# detector.net
KiCad netlist of a schematic drawn in EAGLE
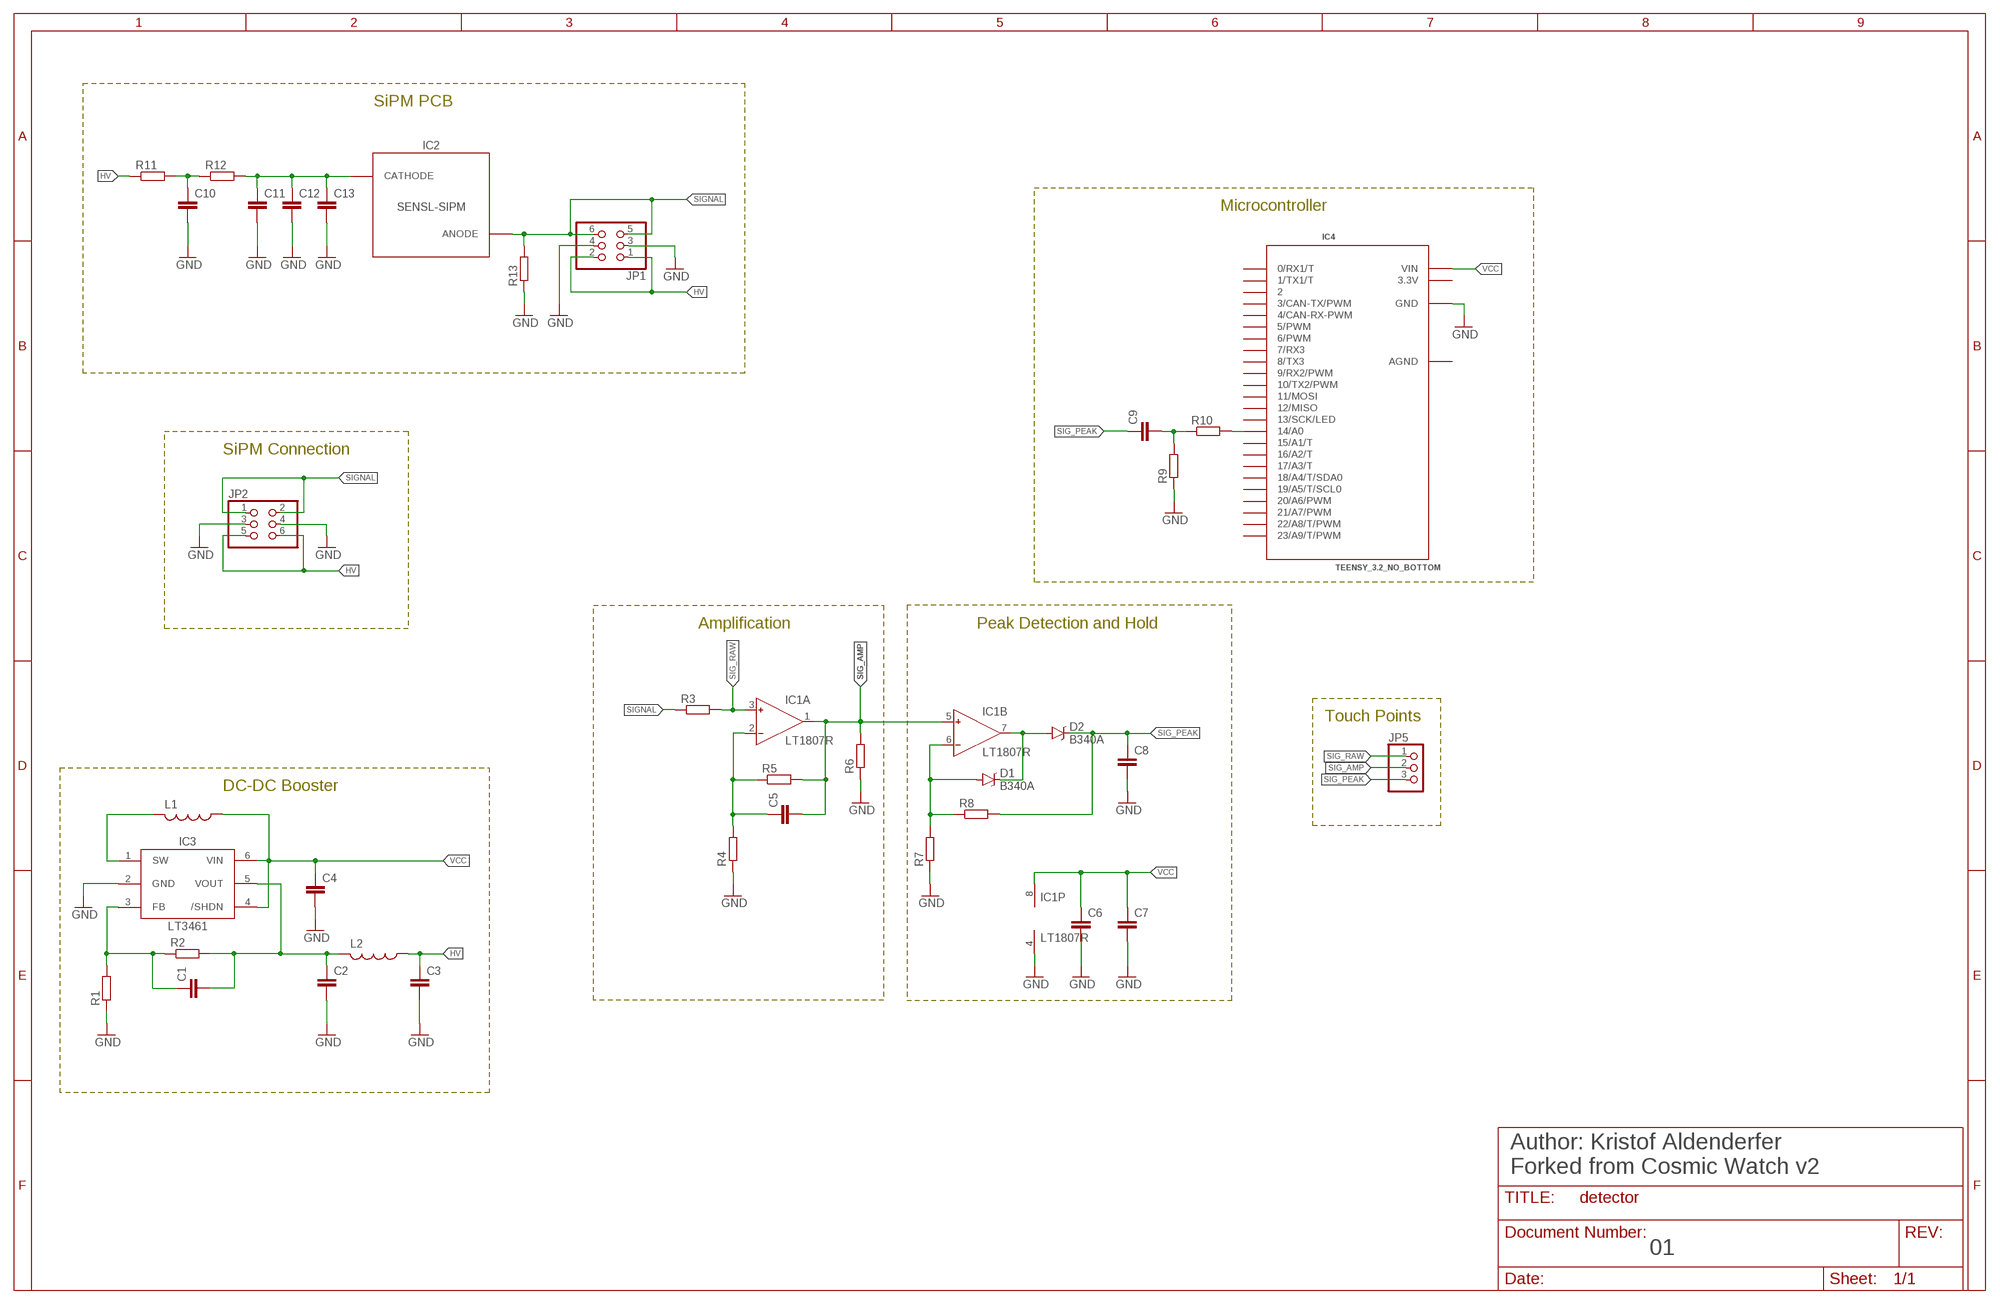
[diagram p0: schematic, sheet 1]

(export (version "E")
  (design (tool "Eeschema 10.0.6"))
  (components
    (comp (ref "C1")
      (value "C-EUC0805")
      (footprint "eagle-import:C0805")
      (libsource (lib "eagle-import") (part "C-EUC0805"))
    )
    (comp (ref "C2")
      (value "C-EUC0805")
      (footprint "eagle-import:C0805")
      (libsource (lib "eagle-import") (part "C-EUC0805"))
    )
    (comp (ref "C3")
      (value "C-EUC0805")
      (footprint "eagle-import:C0805")
      (libsource (lib "eagle-import") (part "C-EUC0805"))
    )
    (comp (ref "C4")
      (value "C-EUC0805")
      (footprint "eagle-import:C0805")
      (libsource (lib "eagle-import") (part "C-EUC0805"))
    )
    (comp (ref "C5")
      (value "C-EUC0805")
      (footprint "eagle-import:C0805")
      (libsource (lib "eagle-import") (part "C-EUC0805"))
    )
    (comp (ref "C6")
      (value "C-EUC0805")
      (footprint "eagle-import:C0805")
      (libsource (lib "eagle-import") (part "C-EUC0805"))
    )
    (comp (ref "C7")
      (value "C-EUC0805")
      (footprint "eagle-import:C0805")
      (libsource (lib "eagle-import") (part "C-EUC0805"))
    )
    (comp (ref "C8")
      (value "C-EUC0805")
      (footprint "eagle-import:C0805")
      (libsource (lib "eagle-import") (part "C-EUC0805"))
    )
    (comp (ref "C9")
      (value "C-EUC0805")
      (footprint "eagle-import:C0805")
      (libsource (lib "eagle-import") (part "C-EUC0805"))
    )
    (comp (ref "C10")
      (value "C-EUC0805")
      (footprint "eagle-import:C0805")
      (libsource (lib "eagle-import") (part "C-EUC0805"))
    )
    (comp (ref "C11")
      (value "C-EUC0805")
      (footprint "eagle-import:C0805")
      (libsource (lib "eagle-import") (part "C-EUC0805"))
    )
    (comp (ref "C12")
      (value "C-EUC0805")
      (footprint "eagle-import:C0805")
      (libsource (lib "eagle-import") (part "C-EUC0805"))
    )
    (comp (ref "C13")
      (value "C-EUC0805")
      (footprint "eagle-import:C0805")
      (libsource (lib "eagle-import") (part "C-EUC0805"))
    )
    (comp (ref "D1")
      (value "B340A")
      (footprint "eagle-import:SMA-DIODE")
      (libsource (lib "eagle-import") (part "DIODE-SCHOTTKY-B340A"))
    )
    (comp (ref "D2")
      (value "B340A")
      (footprint "eagle-import:SMA-DIODE")
      (libsource (lib "eagle-import") (part "DIODE-SCHOTTKY-B340A"))
    )
    (comp (ref "IC1")
      (value "LT1807R")
      (footprint "eagle-import:SO8")
      (fields (field (name "MF") "ALTERA CORPORATION") (field (name "MPN") "AD746JRZ"))
      (libsource (lib "eagle-import") (part "LT1807R"))
    )
    (comp (ref "IC2")
      (value "SENSL-SIPM")
      (footprint "eagle-import:MICROFC-60035")
      (libsource (lib "eagle-import") (part "SENSL-SIPM"))
    )
    (comp (ref "IC3")
      (value "LT3461")
      (footprint "eagle-import:SOT23-6")
      (libsource (lib "eagle-import") (part "LT3461"))
    )
    (comp (ref "IC4")
      (value "TEENSY_3.2_NO_BOTTOM")
      (footprint "eagle-import:TEENSY_3.2_NO_BOTTOM")
      (libsource (lib "eagle-import") (part "TEENSY_3.2_NO_BOTTOM"))
    )
    (comp (ref "JP1")
      (value "PINHD-2X3")
      (footprint "eagle-import:2X03")
      (libsource (lib "eagle-import") (part "PINHD-2X3"))
    )
    (comp (ref "JP2")
      (value "PINHD-2X3")
      (footprint "eagle-import:2X03")
      (libsource (lib "eagle-import") (part "PINHD-2X3"))
    )
    (comp (ref "JP5")
      (value "PINHD-1X3")
      (footprint "eagle-import:1X03")
      (libsource (lib "eagle-import") (part "PINHD-1X3"))
    )
    (comp (ref "L1")
      (value "L-USL2012C")
      (footprint "eagle-import:L2012C")
      (libsource (lib "eagle-import") (part "L-USL2012C"))
    )
    (comp (ref "L2")
      (value "L-USL2012C")
      (footprint "eagle-import:L2012C")
      (libsource (lib "eagle-import") (part "L-USL2012C"))
    )
    (comp (ref "R1")
      (value "R-EU_M0805")
      (footprint "eagle-import:M0805")
      (libsource (lib "eagle-import") (part "R-EU_M0805"))
    )
    (comp (ref "R2")
      (value "R-EU_M0805")
      (footprint "eagle-import:M0805")
      (libsource (lib "eagle-import") (part "R-EU_M0805"))
    )
    (comp (ref "R3")
      (value "R-EU_M0805")
      (footprint "eagle-import:M0805")
      (libsource (lib "eagle-import") (part "R-EU_M0805"))
    )
    (comp (ref "R4")
      (value "R-EU_M0805")
      (footprint "eagle-import:M0805")
      (libsource (lib "eagle-import") (part "R-EU_M0805"))
    )
    (comp (ref "R5")
      (value "R-EU_M0805")
      (footprint "eagle-import:M0805")
      (libsource (lib "eagle-import") (part "R-EU_M0805"))
    )
    (comp (ref "R6")
      (value "R-EU_M0805")
      (footprint "eagle-import:M0805")
      (libsource (lib "eagle-import") (part "R-EU_M0805"))
    )
    (comp (ref "R7")
      (value "R-EU_M0805")
      (footprint "eagle-import:M0805")
      (libsource (lib "eagle-import") (part "R-EU_M0805"))
    )
    (comp (ref "R8")
      (value "R-EU_M0805")
      (footprint "eagle-import:M0805")
      (libsource (lib "eagle-import") (part "R-EU_M0805"))
    )
    (comp (ref "R9")
      (value "R-EU_M0805")
      (footprint "eagle-import:M0805")
      (libsource (lib "eagle-import") (part "R-EU_M0805"))
    )
    (comp (ref "R10")
      (value "R-EU_M0805")
      (footprint "eagle-import:M0805")
      (libsource (lib "eagle-import") (part "R-EU_M0805"))
    )
    (comp (ref "R11")
      (value "R-EU_M0805")
      (footprint "eagle-import:M0805")
      (libsource (lib "eagle-import") (part "R-EU_M0805"))
    )
    (comp (ref "R12")
      (value "R-EU_M0805")
      (footprint "eagle-import:M0805")
      (libsource (lib "eagle-import") (part "R-EU_M0805"))
    )
    (comp (ref "R13")
      (value "R-EU_M0805")
      (footprint "eagle-import:M0805")
      (libsource (lib "eagle-import") (part "R-EU_M0805"))
    )
  )
  (nets
    (net (code "1") (name "/3.3V") (class "Default")
      (node (ref "IC4") (pin "3.3V") (pinfunction "3.3V_3.3V") (pintype "power_in"))
    )
    (net (code "2") (name "/AGND") (class "Default")
      (node (ref "IC4") (pin "AGND") (pinfunction "AGND_AGND") (pintype "power_in"))
    )
    (net (code "3") (name "GND") (class "Default")
      (node (ref "C10") (pin "2") (pinfunction "2_2") (pintype "passive"))
      (node (ref "C11") (pin "2") (pinfunction "2_2") (pintype "passive"))
      (node (ref "C12") (pin "2") (pinfunction "2_2") (pintype "passive"))
      (node (ref "C13") (pin "2") (pinfunction "2_2") (pintype "passive"))
      (node (ref "C2") (pin "2") (pinfunction "2_2") (pintype "passive"))
      (node (ref "C3") (pin "2") (pinfunction "2_2") (pintype "passive"))
      (node (ref "C4") (pin "2") (pinfunction "2_2") (pintype "passive"))
      (node (ref "C6") (pin "2") (pinfunction "2_2") (pintype "passive"))
      (node (ref "C7") (pin "2") (pinfunction "2_2") (pintype "passive"))
      (node (ref "C8") (pin "2") (pinfunction "2_2") (pintype "passive"))
      (node (ref "IC1") (pin "4") (pinfunction "V-_4") (pintype "power_in"))
      (node (ref "IC3") (pin "2") (pinfunction "GND_2") (pintype "power_in"))
      (node (ref "IC4") (pin "GND") (pinfunction "GND_GND") (pintype "power_in"))
      (node (ref "JP1") (pin "3") (pinfunction "3_3") (pintype "passive"))
      (node (ref "JP1") (pin "4") (pinfunction "4_4") (pintype "passive"))
      (node (ref "JP2") (pin "3") (pinfunction "3_3") (pintype "passive"))
      (node (ref "JP2") (pin "4") (pinfunction "4_4") (pintype "passive"))
      (node (ref "R1") (pin "1") (pinfunction "1_1") (pintype "passive"))
      (node (ref "R13") (pin "1") (pinfunction "1_1") (pintype "passive"))
      (node (ref "R4") (pin "1") (pinfunction "1_1") (pintype "passive"))
      (node (ref "R6") (pin "1") (pinfunction "1_1") (pintype "passive"))
      (node (ref "R7") (pin "1") (pinfunction "1_1") (pintype "passive"))
      (node (ref "R9") (pin "1") (pinfunction "1_1") (pintype "passive"))
    )
    (net (code "4") (name "HV") (class "Default")
      (node (ref "C3") (pin "1") (pinfunction "1_1") (pintype "passive"))
      (node (ref "JP1") (pin "1") (pinfunction "1_1") (pintype "passive"))
      (node (ref "JP1") (pin "2") (pinfunction "2_2") (pintype "passive"))
      (node (ref "JP2") (pin "5") (pinfunction "5_5") (pintype "passive"))
      (node (ref "JP2") (pin "6") (pinfunction "6_6") (pintype "passive"))
      (node (ref "L2") (pin "1") (pinfunction "1_1") (pintype "passive"))
      (node (ref "R11") (pin "1") (pinfunction "1_1") (pintype "passive"))
    )
    (net (code "5") (name "Net-(C9-Pad2)") (class "Default")
      (node (ref "C9") (pin "2") (pinfunction "2_2") (pintype "passive"))
      (node (ref "R10") (pin "1") (pinfunction "1_1") (pintype "passive"))
      (node (ref "R9") (pin "2") (pinfunction "2_2") (pintype "passive"))
    )
    (net (code "6") (name "Net-(C10-Pad1)") (class "Default")
      (node (ref "C10") (pin "1") (pinfunction "1_1") (pintype "passive"))
      (node (ref "R11") (pin "2") (pinfunction "2_2") (pintype "passive"))
      (node (ref "R12") (pin "1") (pinfunction "1_1") (pintype "passive"))
    )
    (net (code "7") (name "Net-(C11-Pad1)") (class "Default")
      (node (ref "C11") (pin "1") (pinfunction "1_1") (pintype "passive"))
      (node (ref "C12") (pin "1") (pinfunction "1_1") (pintype "passive"))
      (node (ref "C13") (pin "1") (pinfunction "1_1") (pintype "passive"))
      (node (ref "IC2") (pin "CATHODE") (pinfunction "CATHODE_CATHODE") (pintype "bidirectional"))
      (node (ref "R12") (pin "2") (pinfunction "2_2") (pintype "passive"))
    )
    (net (code "8") (name "Net-(IC1A-IN-)") (class "Default")
      (node (ref "C5") (pin "1") (pinfunction "1_1") (pintype "passive"))
      (node (ref "IC1") (pin "2") (pinfunction "IN-_2") (pintype "input"))
      (node (ref "R4") (pin "2") (pinfunction "2_2") (pintype "passive"))
      (node (ref "R5") (pin "1") (pinfunction "1_1") (pintype "passive"))
    )
    (net (code "9") (name "Net-(IC1B-IN-)") (class "Default")
      (node (ref "D1") (pin "A") (pinfunction "A_A") (pintype "passive"))
      (node (ref "IC1") (pin "6") (pinfunction "IN-_6") (pintype "input"))
      (node (ref "R7") (pin "2") (pinfunction "2_2") (pintype "passive"))
      (node (ref "R8") (pin "1") (pinfunction "1_1") (pintype "passive"))
    )
    (net (code "10") (name "Net-(IC1B-OUT)") (class "Default")
      (node (ref "D1") (pin "C") (pinfunction "C_C") (pintype "passive"))
      (node (ref "D2") (pin "A") (pinfunction "A_A") (pintype "passive"))
      (node (ref "IC1") (pin "7") (pinfunction "OUT_7") (pintype "output"))
    )
    (net (code "11") (name "Net-(IC3-FB)") (class "Default")
      (node (ref "C1") (pin "1") (pinfunction "1_1") (pintype "passive"))
      (node (ref "IC3") (pin "3") (pinfunction "FB_3") (pintype "input"))
      (node (ref "R1") (pin "2") (pinfunction "2_2") (pintype "passive"))
      (node (ref "R2") (pin "1") (pinfunction "1_1") (pintype "passive"))
    )
    (net (code "12") (name "Net-(IC3-SW)") (class "Default")
      (node (ref "IC3") (pin "1") (pinfunction "SW_1") (pintype "output"))
      (node (ref "L1") (pin "2") (pinfunction "2_2") (pintype "passive"))
    )
    (net (code "13") (name "Net-(IC3-VOUT)") (class "Default")
      (node (ref "C1") (pin "2") (pinfunction "2_2") (pintype "passive"))
      (node (ref "C2") (pin "1") (pinfunction "1_1") (pintype "passive"))
      (node (ref "IC3") (pin "5") (pinfunction "VOUT_5") (pintype "output"))
      (node (ref "L2") (pin "2") (pinfunction "2_2") (pintype "passive"))
      (node (ref "R2") (pin "2") (pinfunction "2_2") (pintype "passive"))
    )
    (net (code "14") (name "Net-(IC4-Pad14{slash}A0)") (class "Default")
      (node (ref "IC4") (pin "14/A0") (pinfunction "14/A0_14/A0") (pintype "bidirectional"))
      (node (ref "R10") (pin "2") (pinfunction "2_2") (pintype "passive"))
    )
    (net (code "15") (name "SIGNAL") (class "Default")
      (node (ref "IC2") (pin "ANODE") (pinfunction "ANODE_ANODE") (pintype "bidirectional"))
      (node (ref "JP1") (pin "5") (pinfunction "5_5") (pintype "passive"))
      (node (ref "JP1") (pin "6") (pinfunction "6_6") (pintype "passive"))
      (node (ref "JP2") (pin "1") (pinfunction "1_1") (pintype "passive"))
      (node (ref "JP2") (pin "2") (pinfunction "2_2") (pintype "passive"))
      (node (ref "R13") (pin "2") (pinfunction "2_2") (pintype "passive"))
      (node (ref "R3") (pin "1") (pinfunction "1_1") (pintype "passive"))
    )
    (net (code "16") (name "SIG_AMP") (class "Default")
      (node (ref "C5") (pin "2") (pinfunction "2_2") (pintype "passive"))
      (node (ref "IC1") (pin "1") (pinfunction "OUT_1") (pintype "output"))
      (node (ref "IC1") (pin "5") (pinfunction "IN+_5") (pintype "input"))
      (node (ref "JP5") (pin "2") (pinfunction "2_2") (pintype "passive"))
      (node (ref "R5") (pin "2") (pinfunction "2_2") (pintype "passive"))
      (node (ref "R6") (pin "2") (pinfunction "2_2") (pintype "passive"))
    )
    (net (code "17") (name "SIG_PEAK") (class "Default")
      (node (ref "C8") (pin "1") (pinfunction "1_1") (pintype "passive"))
      (node (ref "C9") (pin "1") (pinfunction "1_1") (pintype "passive"))
      (node (ref "D2") (pin "C") (pinfunction "C_C") (pintype "passive"))
      (node (ref "JP5") (pin "3") (pinfunction "3_3") (pintype "passive"))
      (node (ref "R8") (pin "2") (pinfunction "2_2") (pintype "passive"))
    )
    (net (code "18") (name "SIG_RAW") (class "Default")
      (node (ref "IC1") (pin "3") (pinfunction "IN+_3") (pintype "input"))
      (node (ref "JP5") (pin "1") (pinfunction "1_1") (pintype "passive"))
      (node (ref "R3") (pin "2") (pinfunction "2_2") (pintype "passive"))
    )
    (net (code "19") (name "VCC") (class "Default")
      (node (ref "C4") (pin "1") (pinfunction "1_1") (pintype "passive"))
      (node (ref "C6") (pin "1") (pinfunction "1_1") (pintype "passive"))
      (node (ref "C7") (pin "1") (pinfunction "1_1") (pintype "passive"))
      (node (ref "IC1") (pin "8") (pinfunction "V+_8") (pintype "power_in"))
      (node (ref "IC3") (pin "4") (pinfunction "/SHDN_4") (pintype "input"))
      (node (ref "IC3") (pin "6") (pinfunction "VIN_6") (pintype "input"))
      (node (ref "IC4") (pin "VIN") (pinfunction "VIN_VIN") (pintype "power_in"))
      (node (ref "L1") (pin "1") (pinfunction "1_1") (pintype "passive"))
    )
    (net (code "20") (name "unconnected-(IC4-0{slash}RX1{slash}T-Pad0)") (class "Default")
      (node (ref "IC4") (pin "0") (pinfunction "0/RX1/T_0") (pintype "bidirectional"))
    )
    (net (code "21") (name "unconnected-(IC4-1{slash}TX1{slash}T-Pad1)") (class "Default")
      (node (ref "IC4") (pin "1") (pinfunction "1/TX1/T_1") (pintype "bidirectional"))
    )
    (net (code "22") (name "unconnected-(IC4-3{slash}CAN-TX{slash}PWM-Pad3)") (class "Default")
      (node (ref "IC4") (pin "3") (pinfunction "3/CAN-TX/PWM_3") (pintype "bidirectional"))
    )
    (net (code "23") (name "unconnected-(IC4-4{slash}CAN-RX-PWM-Pad4)") (class "Default")
      (node (ref "IC4") (pin "4") (pinfunction "4/CAN-RX-PWM_4") (pintype "bidirectional"))
    )
    (net (code "24") (name "unconnected-(IC4-5{slash}PWM-Pad5)") (class "Default")
      (node (ref "IC4") (pin "5") (pinfunction "5/PWM_5") (pintype "bidirectional"))
    )
    (net (code "25") (name "unconnected-(IC4-6{slash}PWM-Pad6)") (class "Default")
      (node (ref "IC4") (pin "6") (pinfunction "6/PWM_6") (pintype "bidirectional"))
    )
    (net (code "26") (name "unconnected-(IC4-7{slash}RX3-Pad7)") (class "Default")
      (node (ref "IC4") (pin "7") (pinfunction "7/RX3_7") (pintype "bidirectional"))
    )
    (net (code "27") (name "unconnected-(IC4-8{slash}TX3-Pad8)") (class "Default")
      (node (ref "IC4") (pin "8") (pinfunction "8/TX3_8") (pintype "bidirectional"))
    )
    (net (code "28") (name "unconnected-(IC4-9{slash}RX2{slash}PWM-Pad9)") (class "Default")
      (node (ref "IC4") (pin "9") (pinfunction "9/RX2/PWM_9") (pintype "bidirectional"))
    )
    (net (code "29") (name "unconnected-(IC4-10{slash}TX2{slash}PWM-Pad10)") (class "Default")
      (node (ref "IC4") (pin "10") (pinfunction "10/TX2/PWM_10") (pintype "bidirectional"))
    )
    (net (code "30") (name "unconnected-(IC4-11{slash}MOSI-Pad11)") (class "Default")
      (node (ref "IC4") (pin "11") (pinfunction "11/MOSI_11") (pintype "bidirectional"))
    )
    (net (code "31") (name "unconnected-(IC4-12{slash}MISO-Pad12)") (class "Default")
      (node (ref "IC4") (pin "12") (pinfunction "12/MISO_12") (pintype "bidirectional"))
    )
    (net (code "32") (name "unconnected-(IC4-13{slash}SCK{slash}LED-Pad13)") (class "Default")
      (node (ref "IC4") (pin "13") (pinfunction "13/SCK/LED_13") (pintype "bidirectional"))
    )
    (net (code "33") (name "unconnected-(IC4-15{slash}A1{slash}T-Pad15{slash}A1)") (class "Default")
      (node (ref "IC4") (pin "15/A1") (pinfunction "15/A1/T_15/A1") (pintype "bidirectional"))
    )
    (net (code "34") (name "unconnected-(IC4-16{slash}A2{slash}T-Pad16{slash}A2)") (class "Default")
      (node (ref "IC4") (pin "16/A2") (pinfunction "16/A2/T_16/A2") (pintype "bidirectional"))
    )
    (net (code "35") (name "unconnected-(IC4-17{slash}A3{slash}T-Pad17{slash}A3)") (class "Default")
      (node (ref "IC4") (pin "17/A3") (pinfunction "17/A3/T_17/A3") (pintype "bidirectional"))
    )
    (net (code "36") (name "unconnected-(IC4-18{slash}A4{slash}T{slash}SDA0-Pad18{slash}A4)") (class "Default")
      (node (ref "IC4") (pin "18/A4") (pinfunction "18/A4/T/SDA0_18/A4") (pintype "bidirectional"))
    )
    (net (code "37") (name "unconnected-(IC4-19{slash}A5{slash}T{slash}SCL0-Pad19{slash}A5)") (class "Default")
      (node (ref "IC4") (pin "19/A5") (pinfunction "19/A5/T/SCL0_19/A5") (pintype "bidirectional"))
    )
    (net (code "38") (name "unconnected-(IC4-20{slash}A6{slash}PWM-Pad20{slash}A6)") (class "Default")
      (node (ref "IC4") (pin "20/A6") (pinfunction "20/A6/PWM_20/A6") (pintype "bidirectional"))
    )
    (net (code "39") (name "unconnected-(IC4-21{slash}A7{slash}PWM-Pad21{slash}A7)") (class "Default")
      (node (ref "IC4") (pin "21/A7") (pinfunction "21/A7/PWM_21/A7") (pintype "bidirectional"))
    )
    (net (code "40") (name "unconnected-(IC4-22{slash}A8{slash}T{slash}PWM-Pad22{slash}A8)") (class "Default")
      (node (ref "IC4") (pin "22/A8") (pinfunction "22/A8/T/PWM_22/A8") (pintype "bidirectional"))
    )
    (net (code "41") (name "unconnected-(IC4-23{slash}A9{slash}T{slash}PWM-Pad23{slash}A9)") (class "Default")
      (node (ref "IC4") (pin "23/A9") (pinfunction "23/A9/T/PWM_23/A9") (pintype "bidirectional"))
    )
    (net (code "42") (name "unconnected-(IC4-Pad2)") (class "Default")
      (node (ref "IC4") (pin "2") (pinfunction "2_2") (pintype "bidirectional"))
    )
  )
)
